# TPS26600_test.net
KiCad netlist of a schematic drawn in EAGLE
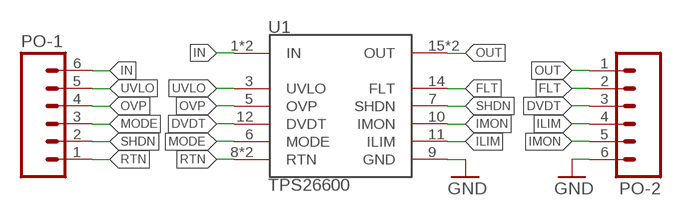
[diagram p0: schematic, sheet 1]

(export (version "E")
  (design (tool "Eeschema 10.0.6"))
  (components
    (comp (ref "PO-1")
      (value "M06")
      (footprint "eagle-import:1X06")
      (libsource (lib "eagle-import") (part "M06"))
    )
    (comp (ref "PO-2")
      (value "M06")
      (footprint "eagle-import:1X06")
      (libsource (lib "eagle-import") (part "M06"))
    )
    (comp (ref "U1")
      (value "TPS26600")
      (footprint "eagle-import:HTSSOP-16")
      (libsource (lib "eagle-import") (part "TPS26600"))
    )
  )
  (nets
    (net (code "1") (name "DVDT") (class "Default")
      (node (ref "PO-2") (pin "3") (pinfunction "3_3") (pintype "passive"))
      (node (ref "U1") (pin "12") (pinfunction "DVDT_12") (pintype "bidirectional"))
    )
    (net (code "2") (name "FLT") (class "Default")
      (node (ref "PO-2") (pin "2") (pinfunction "2_2") (pintype "passive"))
      (node (ref "U1") (pin "14") (pinfunction "FLT_14") (pintype "bidirectional"))
    )
    (net (code "3") (name "GND") (class "Default")
      (node (ref "PO-2") (pin "6") (pinfunction "6_6") (pintype "passive"))
      (node (ref "U1") (pin "9") (pinfunction "GND_9") (pintype "bidirectional"))
    )
    (net (code "4") (name "ILIM") (class "Default")
      (node (ref "PO-2") (pin "4") (pinfunction "4_4") (pintype "passive"))
      (node (ref "U1") (pin "11") (pinfunction "ILIM_11") (pintype "bidirectional"))
    )
    (net (code "5") (name "IMON") (class "Default")
      (node (ref "PO-2") (pin "5") (pinfunction "5_5") (pintype "passive"))
      (node (ref "U1") (pin "10") (pinfunction "IMON_10") (pintype "bidirectional"))
    )
    (net (code "6") (name "IN") (class "Default")
      (node (ref "PO-1") (pin "6") (pinfunction "6_6") (pintype "passive"))
      (node (ref "U1") (pin "1") (pinfunction "IN_1") (pintype "bidirectional"))
      (node (ref "U1") (pin "2") (pinfunction "IN_2") (pintype "bidirectional"))
    )
    (net (code "7") (name "MODE") (class "Default")
      (node (ref "PO-1") (pin "3") (pinfunction "3_3") (pintype "passive"))
      (node (ref "U1") (pin "6") (pinfunction "MODE_6") (pintype "bidirectional"))
    )
    (net (code "8") (name "OUT") (class "Default")
      (node (ref "PO-2") (pin "1") (pinfunction "1_1") (pintype "passive"))
      (node (ref "U1") (pin "15") (pinfunction "OUT_15") (pintype "bidirectional"))
      (node (ref "U1") (pin "16") (pinfunction "OUT_16") (pintype "bidirectional"))
    )
    (net (code "9") (name "OVP") (class "Default")
      (node (ref "PO-1") (pin "4") (pinfunction "4_4") (pintype "passive"))
      (node (ref "U1") (pin "5") (pinfunction "OVP_5") (pintype "bidirectional"))
    )
    (net (code "10") (name "RTN") (class "Default")
      (node (ref "PO-1") (pin "1") (pinfunction "1_1") (pintype "passive"))
      (node (ref "U1") (pin "8") (pinfunction "RTN_8") (pintype "bidirectional"))
      (node (ref "U1") (pin "PAD") (pinfunction "RTN_PAD") (pintype "bidirectional"))
    )
    (net (code "11") (name "SHDN") (class "Default")
      (node (ref "PO-1") (pin "2") (pinfunction "2_2") (pintype "passive"))
      (node (ref "U1") (pin "7") (pinfunction "SHDN_7") (pintype "bidirectional"))
    )
    (net (code "12") (name "UVLO") (class "Default")
      (node (ref "PO-1") (pin "5") (pinfunction "5_5") (pintype "passive"))
      (node (ref "U1") (pin "3") (pinfunction "UVLO_3") (pintype "bidirectional"))
    )
  )
)
